# FCC_MCU.net
KiCad netlist of a schematic drawn in Altium Designer
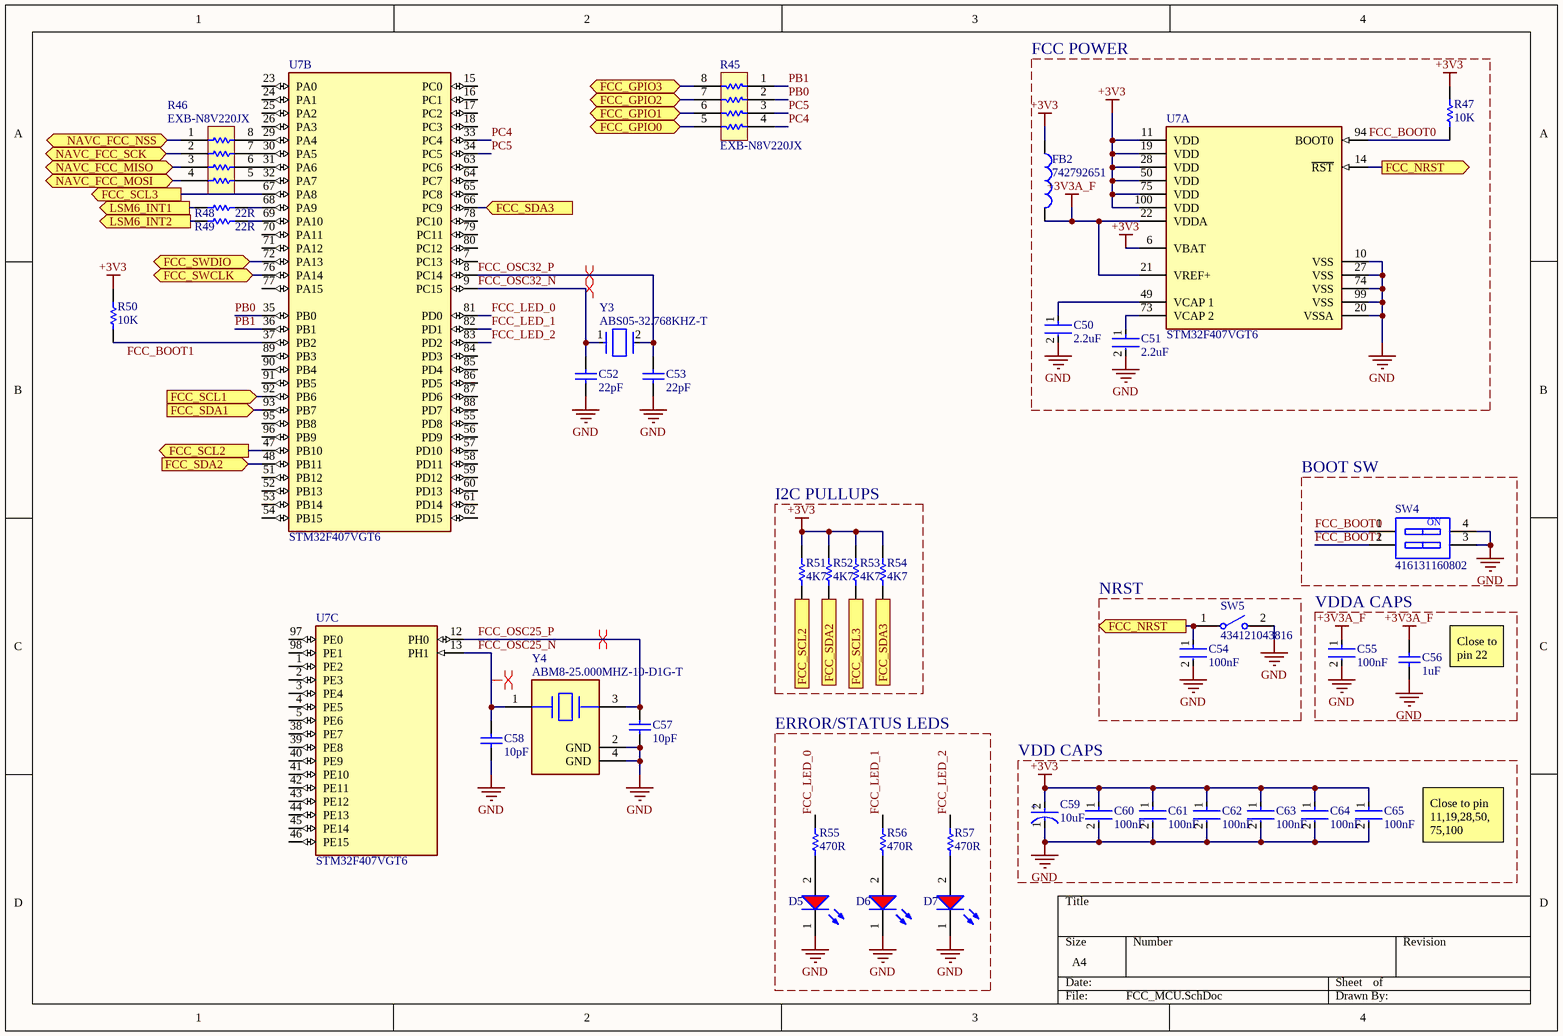
[diagram p0: FCC_MCU.SchDoc]

(export (version "E")
  (design (tool "Eeschema 10.0.6"))
  (components
    (comp (ref "C50")
      (value "2.2uF")
      (footprint "FP-CGA3E-0_3-0_1-IPC_A")
      (description "Cap Ceramic 100nF 50V X7R 10% Pad SMD 0603 +125°C Automotive T/R")
      (fields (field (name "TOLERANCE") "10%") (field (name "VOLTAGE") "50V"))
      (libsource (lib "Altium Content Vault") (part "b4654b650e69147ec39a6b967a45e02"))
    )
    (comp (ref "C51")
      (value "2.2uF")
      (footprint "FP-CGA3E-0_3-0_1-IPC_A")
      (description "Cap Ceramic 100nF 50V X7R 10% Pad SMD 0603 +125°C Automotive T/R")
      (fields (field (name "TOLERANCE") "10%") (field (name "VOLTAGE") "50V"))
      (libsource (lib "Altium Content Vault") (part "b4654b650e69147ec39a6b967a45e02"))
    )
    (comp (ref "C52")
      (value "22pF")
      (footprint "CAPC1608X90X35ML10T15")
      (description "Chip Capacitor, 22 pF, +/- 5%, 50 V, -55 to 125 degC, 0603 (1608 Metric), RoHS, Tape and Reel")
      (fields (field (name "MANUFACTURER") "Murata"))
      (libsource (lib "Altium Content Vault") (part "CAP-NP-2"))
    )
    (comp (ref "C53")
      (value "22pF")
      (footprint "CAPC1608X90X35ML10T15")
      (description "Chip Capacitor, 22 pF, +/- 5%, 50 V, -55 to 125 degC, 0603 (1608 Metric), RoHS, Tape and Reel")
      (fields (field (name "MANUFACTURER") "Murata"))
      (libsource (lib "Altium Content Vault") (part "CAP-NP-2"))
    )
    (comp (ref "C54")
      (value "100nF")
      (footprint "FP-CGA3E-0_3-0_1-IPC_A")
      (description "Cap Ceramic 100nF 50V X7R 10% Pad SMD 0603 +125°C Automotive T/R")
      (fields (field (name "TOLERANCE") "10%") (field (name "VOLTAGE") "50V"))
      (libsource (lib "Altium Content Vault") (part "b4654b650e69147ec39a6b967a45e02"))
    )
    (comp (ref "C55")
      (value "100nF")
      (footprint "FP-CGA3E-0_3-0_1-IPC_A")
      (description "Cap Ceramic 100nF 50V X7R 10% Pad SMD 0603 +125°C Automotive T/R")
      (fields (field (name "TOLERANCE") "10%") (field (name "VOLTAGE") "50V"))
      (libsource (lib "Altium Content Vault") (part "b4654b650e69147ec39a6b967a45e02"))
    )
    (comp (ref "C56")
      (value "1uF")
      (footprint "CAPC1608X87X35LL15T15")
      (fields (field (name "PART NUMBER") "C0603C105K3RACTU") (field (name "MANUFACTURER") "Kemet"))
      (libsource (lib "Altium Content Vault") (part "CAP"))
    )
    (comp (ref "C57")
      (value "10pF")
      (footprint "CAPC1608X90X35LL10T15")
      (fields (field (name "PART NUMBER") "GRM1885C1H100JA01D") (field (name "MANUFACTURER") "Murata"))
      (libsource (lib "Altium Content Vault") (part "CAP"))
    )
    (comp (ref "C58")
      (value "10pF")
      (footprint "CAPC1608X90X35LL10T15")
      (fields (field (name "PART NUMBER") "GRM1885C1H100JA01D") (field (name "MANUFACTURER") "Murata"))
      (libsource (lib "Altium Content Vault") (part "CAP"))
    )
    (comp (ref "C59")
      (value "10uF")
      (footprint "FP-T491A106K006AT-MFG")
      (description "CAP TANT 10UF 10% 6.3V 1206")
      (fields (field (name "TOLERANCE") "10%") (field (name "VOLTAGE") "6.3V"))
      (libsource (lib "Altium Content Vault") (part "a00bbbee19879c290e62620ae7e47b1"))
    )
    (comp (ref "C60")
      (value "100nF")
      (footprint "FP-CGA3E-0_3-0_1-IPC_A")
      (description "Cap Ceramic 100nF 50V X7R 10% Pad SMD 0603 +125°C Automotive T/R")
      (fields (field (name "TOLERANCE") "10%") (field (name "VOLTAGE") "50V"))
      (libsource (lib "Altium Content Vault") (part "b4654b650e69147ec39a6b967a45e02"))
    )
    (comp (ref "C61")
      (value "100nF")
      (footprint "FP-CGA3E-0_3-0_1-IPC_A")
      (description "Cap Ceramic 100nF 50V X7R 10% Pad SMD 0603 +125°C Automotive T/R")
      (fields (field (name "TOLERANCE") "10%") (field (name "VOLTAGE") "50V"))
      (libsource (lib "Altium Content Vault") (part "b4654b650e69147ec39a6b967a45e02"))
    )
    (comp (ref "C62")
      (value "100nF")
      (footprint "FP-CGA3E-0_3-0_1-IPC_A")
      (description "Cap Ceramic 100nF 50V X7R 10% Pad SMD 0603 +125°C Automotive T/R")
      (fields (field (name "TOLERANCE") "10%") (field (name "VOLTAGE") "50V"))
      (libsource (lib "Altium Content Vault") (part "b4654b650e69147ec39a6b967a45e02"))
    )
    (comp (ref "C63")
      (value "100nF")
      (footprint "FP-CGA3E-0_3-0_1-IPC_A")
      (description "Cap Ceramic 100nF 50V X7R 10% Pad SMD 0603 +125°C Automotive T/R")
      (fields (field (name "TOLERANCE") "10%") (field (name "VOLTAGE") "50V"))
      (libsource (lib "Altium Content Vault") (part "b4654b650e69147ec39a6b967a45e02"))
    )
    (comp (ref "C64")
      (value "100nF")
      (footprint "FP-CGA3E-0_3-0_1-IPC_A")
      (description "Cap Ceramic 100nF 50V X7R 10% Pad SMD 0603 +125°C Automotive T/R")
      (fields (field (name "TOLERANCE") "10%") (field (name "VOLTAGE") "50V"))
      (libsource (lib "Altium Content Vault") (part "b4654b650e69147ec39a6b967a45e02"))
    )
    (comp (ref "C65")
      (value "100nF")
      (footprint "FP-CGA3E-0_3-0_1-IPC_A")
      (description "Cap Ceramic 100nF 50V X7R 10% Pad SMD 0603 +125°C Automotive T/R")
      (fields (field (name "TOLERANCE") "10%") (field (name "VOLTAGE") "50V"))
      (libsource (lib "Altium Content Vault") (part "b4654b650e69147ec39a6b967a45e02"))
    )
    (comp (ref "D5")
      (value "150120SS75000")
      (footprint "WL-SMCW_1206_150120xx75000")
      (description "Led, Red, 630 Nm, 1.9 V, 30 Ma, 60 Mcd Rohs Compliant: Yes")
      (libsource (lib "Altium Content Vault") (part "LED_Red_2A-1K"))
    )
    (comp (ref "D6")
      (value "150120SS75000")
      (footprint "WL-SMCW_1206_150120xx75000")
      (description "Led, Red, 630 Nm, 1.9 V, 30 Ma, 60 Mcd Rohs Compliant: Yes")
      (libsource (lib "Altium Content Vault") (part "LED_Red_2A-1K"))
    )
    (comp (ref "D7")
      (value "150120SS75000")
      (footprint "WL-SMCW_1206_150120xx75000")
      (description "Led, Red, 630 Nm, 1.9 V, 30 Ma, 60 Mcd Rohs Compliant: Yes")
      (libsource (lib "Altium Content Vault") (part "LED_Red_2A-1K"))
    )
    (comp (ref "FB2")
      (value "742792651")
      (footprint "WE-CBF_0603_L1.6W0.8H0.8_HC")
      (fields (field (name "TOLERANCE") "25%"))
      (libsource (lib "Altium Content Vault") (part "Ferrite"))
    )
    (comp (ref "R45")
      (value "EXB-N8V220JX")
      (footprint "BOUR-CAT10_V")
      (description "Chip Resistor Array, 22 Ohm, +/- 5%, -55 to 125 degC, 8-Pin SMD, RoHS, Tape and Reel")
      (fields (field (name "MANUFACTURER") "Bourns") (field (name "TOLERANCE") "±5%"))
      (libsource (lib "Altium Content Vault") (part "RES-P-8"))
    )
    (comp (ref "R46")
      (value "EXB-N8V220JX")
      (footprint "BOUR-CAT10_V")
      (description "Chip Resistor Array, 22 Ohm, +/- 5%, -55 to 125 degC, 8-Pin SMD, RoHS, Tape and Reel")
      (fields (field (name "MANUFACTURER") "Bourns") (field (name "TOLERANCE") "±5%"))
      (libsource (lib "") (part "RES-P-8_1"))
    )
    (comp (ref "R47")
      (value "10K")
      (footprint "RESC1608X55X25ML10T15")
      (description "Chip Resistor, 0 Ohm, +/- 5%, 0.1 W, -55 to 155 degC, 0603 (1608 Metric), RoHS, Tape and Reel")
      (fields (field (name "TOLERANCE") "5%") (field (name "MANUFACTURER") "Yageo"))
      (libsource (lib "Altium Content Vault") (part "RES-2"))
    )
    (comp (ref "R48")
      (value "22R")
      (footprint "RESC1608X55X25ML10T15")
      (description "Chip Resistor, 0 Ohm, +/- 5%, 0.1 W, -55 to 155 degC, 0603 (1608 Metric), RoHS, Tape and Reel")
      (fields (field (name "TOLERANCE") "5%") (field (name "MANUFACTURER") "Yageo"))
      (libsource (lib "Altium Content Vault") (part "RES-2"))
    )
    (comp (ref "R49")
      (value "22R")
      (footprint "RESC1608X55X25ML10T15")
      (description "Chip Resistor, 0 Ohm, +/- 5%, 0.1 W, -55 to 155 degC, 0603 (1608 Metric), RoHS, Tape and Reel")
      (fields (field (name "TOLERANCE") "5%") (field (name "MANUFACTURER") "Yageo"))
      (libsource (lib "Altium Content Vault") (part "RES-2"))
    )
    (comp (ref "R50")
      (value "10K")
      (footprint "RESC1608X55X25ML10T15")
      (description "Chip Resistor, 0 Ohm, +/- 5%, 0.1 W, -55 to 155 degC, 0603 (1608 Metric), RoHS, Tape and Reel")
      (fields (field (name "TOLERANCE") "5%") (field (name "MANUFACTURER") "Yageo"))
      (libsource (lib "Altium Content Vault") (part "RES-2"))
    )
    (comp (ref "R51")
      (value "4K7")
      (footprint "RESC1608X55X25ML10T15")
      (description "Chip Resistor, 0 Ohm, +/- 5%, 0.1 W, -55 to 155 degC, 0603 (1608 Metric), RoHS, Tape and Reel")
      (fields (field (name "TOLERANCE") "5%") (field (name "MANUFACTURER") "Yageo"))
      (libsource (lib "Altium Content Vault") (part "RES-2"))
    )
    (comp (ref "R52")
      (value "4K7")
      (footprint "RESC1608X55X25ML10T15")
      (description "Chip Resistor, 0 Ohm, +/- 5%, 0.1 W, -55 to 155 degC, 0603 (1608 Metric), RoHS, Tape and Reel")
      (fields (field (name "TOLERANCE") "5%") (field (name "MANUFACTURER") "Yageo"))
      (libsource (lib "Altium Content Vault") (part "RES-2"))
    )
    (comp (ref "R53")
      (value "4K7")
      (footprint "RESC1608X55X25ML10T15")
      (description "Chip Resistor, 0 Ohm, +/- 5%, 0.1 W, -55 to 155 degC, 0603 (1608 Metric), RoHS, Tape and Reel")
      (fields (field (name "TOLERANCE") "5%") (field (name "MANUFACTURER") "Yageo"))
      (libsource (lib "Altium Content Vault") (part "RES-2"))
    )
    (comp (ref "R54")
      (value "4K7")
      (footprint "RESC1608X55X25ML10T15")
      (description "Chip Resistor, 0 Ohm, +/- 5%, 0.1 W, -55 to 155 degC, 0603 (1608 Metric), RoHS, Tape and Reel")
      (fields (field (name "TOLERANCE") "5%") (field (name "MANUFACTURER") "Yageo"))
      (libsource (lib "Altium Content Vault") (part "RES-2"))
    )
    (comp (ref "R55")
      (value "470R")
      (footprint "RESC1609X50X30NL8T20")
      (description "Chip Resistor, 0 Ohm, Jumper, 100 mW, -55 to 155 degC, 0603 (1608 Metric), RoHS, Tape and Reel")
      (fields (field (name "MANUFACTURER") "Vishay Semiconductor"))
      (libsource (lib "Altium Content Vault") (part "RES-2"))
    )
    (comp (ref "R56")
      (value "470R")
      (footprint "RESC1609X50X30NL8T20")
      (description "Chip Resistor, 0 Ohm, Jumper, 100 mW, -55 to 155 degC, 0603 (1608 Metric), RoHS, Tape and Reel")
      (fields (field (name "MANUFACTURER") "Vishay Semiconductor"))
      (libsource (lib "Altium Content Vault") (part "RES-2"))
    )
    (comp (ref "R57")
      (value "470R")
      (footprint "RESC1609X50X30NL8T20")
      (description "Chip Resistor, 0 Ohm, Jumper, 100 mW, -55 to 155 degC, 0603 (1608 Metric), RoHS, Tape and Reel")
      (fields (field (name "MANUFACTURER") "Vishay Semiconductor"))
      (libsource (lib "Altium Content Vault") (part "RES-2"))
    )
    (comp (ref "SW4")
      (value "416131160802")
      (footprint "416131160802")
      (libsource (lib "Altium Content Vault") (part "DIP-2"))
    )
    (comp (ref "SW5")
      (value "434121043816")
      (footprint "434121043816")
      (description "Switch Tactile Spst-no 0.05A 12V")
      (libsource (lib "Altium Content Vault") (part "SPST-NO_2P"))
    )
    (comp (ref "U7")
      (value "STM32F407VGT6")
      (footprint "FP-LQFP100-1L-MFG")
      (libsource (lib "Altium Content Vault") (part "a7eb53df74ca670d391abe4a9ac8be5"))
    )
    (comp (ref "Y3")
      (value "ABS05-32.768KHZ-T")
      (footprint "FP-ABS05-MFG")
      (description "Crystal 32.768kHz ±20ppm (Tol) 12.5pF FUND 90kΩ 2-Pin SMD T/R")
      (fields (field (name "TOLERANCE") "20ppm"))
      (libsource (lib "Altium Content Vault") (part "c23a69dc6c9e2f18f2079038eb95dd1"))
    )
    (comp (ref "Y4")
      (value "ABM8-25.000MHZ-10-D1G-T")
      (footprint "FP-ABM8-MFG")
      (description "Crystal 25MHz ±10ppm 10pF SMD-4 3.2mm x 2.5mm")
      (libsource (lib "Altium Content Vault") (part "dfdb7f9a12507849fb681da9a70121c"))
    )
  )
  (nets
    (net (code "1") (name "+3V3") (class "Default")
      (node (ref "C59") (pin "2") (pinfunction "A_2") (pintype "passive"))
      (node (ref "C60") (pin "1") (pinfunction "1_1") (pintype "passive"))
      (node (ref "C61") (pin "1") (pinfunction "1_1") (pintype "passive"))
      (node (ref "C62") (pin "1") (pinfunction "1_1") (pintype "passive"))
      (node (ref "C63") (pin "1") (pinfunction "1_1") (pintype "passive"))
      (node (ref "C64") (pin "1") (pinfunction "1_1") (pintype "passive"))
      (node (ref "C65") (pin "1") (pinfunction "1_1") (pintype "passive"))
      (node (ref "FB2") (pin "1") (pinfunction "1_1") (pintype "passive"))
      (node (ref "R47") (pin "1") (pinfunction "1_1") (pintype "passive"))
      (node (ref "R50") (pin "1") (pinfunction "1_1") (pintype "passive"))
      (node (ref "R51") (pin "2") (pinfunction "2_2") (pintype "passive"))
      (node (ref "R52") (pin "2") (pinfunction "2_2") (pintype "passive"))
      (node (ref "R53") (pin "2") (pinfunction "2_2") (pintype "passive"))
      (node (ref "R54") (pin "2") (pinfunction "2_2") (pintype "passive"))
      (node (ref "U7") (pin "100") (pinfunction "VDD_100") (pintype "power_in"))
      (node (ref "U7") (pin "11") (pinfunction "VDD_11") (pintype "power_in"))
      (node (ref "U7") (pin "19") (pinfunction "VDD_19") (pintype "power_in"))
      (node (ref "U7") (pin "28") (pinfunction "VDD_28") (pintype "power_in"))
      (node (ref "U7") (pin "50") (pinfunction "VDD_50") (pintype "power_in"))
      (node (ref "U7") (pin "6") (pinfunction "VBAT_6") (pintype "power_in"))
      (node (ref "U7") (pin "75") (pinfunction "VDD_75") (pintype "power_in"))
    )
    (net (code "2") (name "+3V3A_F") (class "Default")
      (node (ref "C55") (pin "1") (pinfunction "1_1") (pintype "passive"))
      (node (ref "C56") (pin "2") (pinfunction "2_2") (pintype "passive"))
      (node (ref "FB2") (pin "2") (pinfunction "2_2") (pintype "passive"))
      (node (ref "U7") (pin "21") (pinfunction "VREF+_21") (pintype "power_in"))
      (node (ref "U7") (pin "22") (pinfunction "VDDA_22") (pintype "power_in"))
    )
    (net (code "3") (name "/FCC_BOOT0") (class "Default")
      (node (ref "R47") (pin "2") (pinfunction "2_2") (pintype "passive"))
      (node (ref "SW4") (pin "1") (pinfunction "1_1") (pintype "passive"))
      (node (ref "U7") (pin "94") (pinfunction "BOOT0_94") (pintype "input"))
    )
    (net (code "4") (name "/FCC_BOOT1") (class "Default")
      (node (ref "R50") (pin "2") (pinfunction "2_2") (pintype "passive"))
      (node (ref "SW4") (pin "2") (pinfunction "2_2") (pintype "passive"))
      (node (ref "U7") (pin "37") (pinfunction "PB2_37") (pintype "bidirectional"))
    )
    (net (code "5") (name "/FCC_GPIO0") (class "Default")
      (node (ref "R45") (pin "5") (pinfunction "5_5") (pintype "passive"))
    )
    (net (code "6") (name "/FCC_GPIO1") (class "Default")
      (node (ref "R45") (pin "6") (pinfunction "6_6") (pintype "passive"))
    )
    (net (code "7") (name "/FCC_GPIO2") (class "Default")
      (node (ref "R45") (pin "7") (pinfunction "7_7") (pintype "passive"))
    )
    (net (code "8") (name "/FCC_GPIO3") (class "Default")
      (node (ref "R45") (pin "8") (pinfunction "8_8") (pintype "passive"))
    )
    (net (code "9") (name "/FCC_LED_0") (class "Default")
      (node (ref "R55") (pin "1") (pinfunction "1_1") (pintype "passive"))
      (node (ref "U7") (pin "81") (pinfunction "PD0_81") (pintype "bidirectional"))
    )
    (net (code "10") (name "/FCC_LED_1") (class "Default")
      (node (ref "R56") (pin "1") (pinfunction "1_1") (pintype "passive"))
      (node (ref "U7") (pin "82") (pinfunction "PD1_82") (pintype "bidirectional"))
    )
    (net (code "11") (name "/FCC_LED_2") (class "Default")
      (node (ref "R57") (pin "1") (pinfunction "1_1") (pintype "passive"))
      (node (ref "U7") (pin "83") (pinfunction "PD2_83") (pintype "bidirectional"))
    )
    (net (code "12") (name "/FCC_NRST") (class "Default")
      (node (ref "C54") (pin "1") (pinfunction "1_1") (pintype "passive"))
      (node (ref "SW5") (pin "1") (pinfunction "1_1") (pintype "passive"))
      (node (ref "U7") (pin "14") (pinfunction "~{RST}_14") (pintype "input"))
    )
    (net (code "13") (name "/FCC_OSC25_N") (class "Default")
      (node (ref "C58") (pin "2") (pinfunction "2_2") (pintype "passive"))
      (node (ref "U7") (pin "13") (pinfunction "PH1_13") (pintype "input"))
      (node (ref "Y4") (pin "1") (pinfunction "1_1") (pintype "passive"))
    )
    (net (code "14") (name "/FCC_OSC25_P") (class "Default")
      (node (ref "C57") (pin "2") (pinfunction "2_2") (pintype "passive"))
      (node (ref "U7") (pin "12") (pinfunction "PH0_12") (pintype "bidirectional"))
      (node (ref "Y4") (pin "3") (pinfunction "3_3") (pintype "passive"))
    )
    (net (code "15") (name "/FCC_OSC32_N") (class "Default")
      (node (ref "C52") (pin "2") (pinfunction "2_2") (pintype "passive"))
      (node (ref "U7") (pin "9") (pinfunction "PC15_9") (pintype "bidirectional"))
      (node (ref "Y3") (pin "1") (pinfunction "1_1") (pintype "passive"))
    )
    (net (code "16") (name "/FCC_OSC32_P") (class "Default")
      (node (ref "C53") (pin "2") (pinfunction "2_2") (pintype "passive"))
      (node (ref "U7") (pin "8") (pinfunction "PC14_8") (pintype "bidirectional"))
      (node (ref "Y3") (pin "2") (pinfunction "2_2") (pintype "passive"))
    )
    (net (code "17") (name "/FCC_SCL1") (class "Default")
      (node (ref "U7") (pin "92") (pinfunction "PB6_92") (pintype "bidirectional"))
    )
    (net (code "18") (name "/FCC_SCL2") (class "Default")
      (node (ref "R51") (pin "1") (pinfunction "1_1") (pintype "passive"))
      (node (ref "U7") (pin "47") (pinfunction "PB10_47") (pintype "bidirectional"))
    )
    (net (code "19") (name "/FCC_SCL3") (class "Default")
      (node (ref "R53") (pin "1") (pinfunction "1_1") (pintype "passive"))
      (node (ref "U7") (pin "67") (pinfunction "PA8_67") (pintype "bidirectional"))
    )
    (net (code "20") (name "/FCC_SDA1") (class "Default")
      (node (ref "U7") (pin "93") (pinfunction "PB7_93") (pintype "bidirectional"))
    )
    (net (code "21") (name "/FCC_SDA2") (class "Default")
      (node (ref "R52") (pin "1") (pinfunction "1_1") (pintype "passive"))
      (node (ref "U7") (pin "48") (pinfunction "PB11_48") (pintype "bidirectional"))
    )
    (net (code "22") (name "/FCC_SDA3") (class "Default")
      (node (ref "R54") (pin "1") (pinfunction "1_1") (pintype "passive"))
      (node (ref "U7") (pin "66") (pinfunction "PC9_66") (pintype "bidirectional"))
    )
    (net (code "23") (name "/FCC_SWCLK") (class "Default")
      (node (ref "U7") (pin "76") (pinfunction "PA14_76") (pintype "bidirectional"))
    )
    (net (code "24") (name "/FCC_SWDIO") (class "Default")
      (node (ref "U7") (pin "72") (pinfunction "PA13_72") (pintype "bidirectional"))
    )
    (net (code "25") (name "/LSM6_INT1") (class "Default")
      (node (ref "R48") (pin "1") (pinfunction "1_1") (pintype "passive"))
    )
    (net (code "26") (name "/LSM6_INT2") (class "Default")
      (node (ref "R49") (pin "1") (pinfunction "1_1") (pintype "passive"))
    )
    (net (code "27") (name "/NAVC_FCC_MISO") (class "Default")
      (node (ref "R46") (pin "3") (pinfunction "3_3") (pintype "passive"))
    )
    (net (code "28") (name "/NAVC_FCC_MOSI") (class "Default")
      (node (ref "R46") (pin "4") (pinfunction "4_4") (pintype "passive"))
    )
    (net (code "29") (name "/NAVC_FCC_NSS") (class "Default")
      (node (ref "R46") (pin "1") (pinfunction "1_1") (pintype "passive"))
    )
    (net (code "30") (name "/NAVC_FCC_SCK") (class "Default")
      (node (ref "R46") (pin "2") (pinfunction "2_2") (pintype "passive"))
    )
    (net (code "31") (name "/PB0") (class "Default")
      (node (ref "R45") (pin "2") (pinfunction "2_2") (pintype "passive"))
      (node (ref "U7") (pin "35") (pinfunction "PB0_35") (pintype "bidirectional"))
    )
    (net (code "32") (name "/PB1") (class "Default")
      (node (ref "R45") (pin "1") (pinfunction "1_1") (pintype "passive"))
      (node (ref "U7") (pin "36") (pinfunction "PB1_36") (pintype "bidirectional"))
    )
    (net (code "33") (name "/PC4") (class "Default")
      (node (ref "R45") (pin "4") (pinfunction "4_4") (pintype "passive"))
      (node (ref "U7") (pin "33") (pinfunction "PC4_33") (pintype "bidirectional"))
    )
    (net (code "34") (name "/PC5") (class "Default")
      (node (ref "R45") (pin "3") (pinfunction "3_3") (pintype "passive"))
      (node (ref "U7") (pin "34") (pinfunction "PC5_34") (pintype "bidirectional"))
    )
    (net (code "35") (name "GND") (class "Default")
      (node (ref "C50") (pin "2") (pinfunction "2_2") (pintype "passive"))
      (node (ref "C51") (pin "2") (pinfunction "2_2") (pintype "passive"))
      (node (ref "C52") (pin "1") (pinfunction "1_1") (pintype "passive"))
      (node (ref "C53") (pin "1") (pinfunction "1_1") (pintype "passive"))
      (node (ref "C54") (pin "2") (pinfunction "2_2") (pintype "passive"))
      (node (ref "C55") (pin "2") (pinfunction "2_2") (pintype "passive"))
      (node (ref "C56") (pin "1") (pinfunction "1_1") (pintype "passive"))
      (node (ref "C57") (pin "1") (pinfunction "1_1") (pintype "passive"))
      (node (ref "C58") (pin "1") (pinfunction "1_1") (pintype "passive"))
      (node (ref "C59") (pin "1") (pinfunction "C_1") (pintype "passive"))
      (node (ref "C60") (pin "2") (pinfunction "2_2") (pintype "passive"))
      (node (ref "C61") (pin "2") (pinfunction "2_2") (pintype "passive"))
      (node (ref "C62") (pin "2") (pinfunction "2_2") (pintype "passive"))
      (node (ref "C63") (pin "2") (pinfunction "2_2") (pintype "passive"))
      (node (ref "C64") (pin "2") (pinfunction "2_2") (pintype "passive"))
      (node (ref "C65") (pin "2") (pinfunction "2_2") (pintype "passive"))
      (node (ref "D5") (pin "1") (pinfunction "K_1") (pintype "passive"))
      (node (ref "D6") (pin "1") (pinfunction "K_1") (pintype "passive"))
      (node (ref "D7") (pin "1") (pinfunction "K_1") (pintype "passive"))
      (node (ref "SW4") (pin "3") (pinfunction "3_3") (pintype "passive"))
      (node (ref "SW4") (pin "4") (pinfunction "4_4") (pintype "passive"))
      (node (ref "SW5") (pin "2") (pinfunction "2_2") (pintype "passive"))
      (node (ref "U7") (pin "10") (pinfunction "VSS_10") (pintype "power_in"))
      (node (ref "U7") (pin "20") (pinfunction "VSSA_20") (pintype "power_in"))
      (node (ref "U7") (pin "27") (pinfunction "VSS_27") (pintype "power_in"))
      (node (ref "U7") (pin "74") (pinfunction "VSS_74") (pintype "power_in"))
      (node (ref "U7") (pin "99") (pinfunction "VSS_99") (pintype "power_in"))
      (node (ref "Y4") (pin "2") (pinfunction "GND_2") (pintype "power_in"))
      (node (ref "Y4") (pin "4") (pinfunction "GND_4") (pintype "power_in"))
    )
    (net (code "36") (name "Net-(D5-A)") (class "Default")
      (node (ref "D5") (pin "2") (pinfunction "A_2") (pintype "passive"))
      (node (ref "R55") (pin "2") (pinfunction "2_2") (pintype "passive"))
    )
    (net (code "37") (name "Net-(D6-A)") (class "Default")
      (node (ref "D6") (pin "2") (pinfunction "A_2") (pintype "passive"))
      (node (ref "R56") (pin "2") (pinfunction "2_2") (pintype "passive"))
    )
    (net (code "38") (name "Net-(D7-A)") (class "Default")
      (node (ref "D7") (pin "2") (pinfunction "A_2") (pintype "passive"))
      (node (ref "R57") (pin "2") (pinfunction "2_2") (pintype "passive"))
    )
    (net (code "39") (name "Net-(U7A-VCAP_1)") (class "Default")
      (node (ref "C50") (pin "1") (pinfunction "1_1") (pintype "passive"))
      (node (ref "U7") (pin "49") (pinfunction "VCAP_1_49") (pintype "power_in"))
    )
    (net (code "40") (name "Net-(U7A-VCAP_2)") (class "Default")
      (node (ref "C51") (pin "1") (pinfunction "1_1") (pintype "passive"))
      (node (ref "U7") (pin "73") (pinfunction "VCAP_2_73") (pintype "power_in"))
    )
    (net (code "41") (name "Net-(U7B-PA4)") (class "Default")
      (node (ref "R46") (pin "8") (pinfunction "8_8") (pintype "passive"))
      (node (ref "U7") (pin "29") (pinfunction "PA4_29") (pintype "bidirectional"))
    )
    (net (code "42") (name "Net-(U7B-PA5)") (class "Default")
      (node (ref "R46") (pin "7") (pinfunction "7_7") (pintype "passive"))
      (node (ref "U7") (pin "30") (pinfunction "PA5_30") (pintype "bidirectional"))
    )
    (net (code "43") (name "Net-(U7B-PA6)") (class "Default")
      (node (ref "R46") (pin "6") (pinfunction "6_6") (pintype "passive"))
      (node (ref "U7") (pin "31") (pinfunction "PA6_31") (pintype "bidirectional"))
    )
    (net (code "44") (name "Net-(U7B-PA7)") (class "Default")
      (node (ref "R46") (pin "5") (pinfunction "5_5") (pintype "passive"))
      (node (ref "U7") (pin "32") (pinfunction "PA7_32") (pintype "bidirectional"))
    )
    (net (code "45") (name "Net-(U7B-PA9)") (class "Default")
      (node (ref "R48") (pin "2") (pinfunction "2_2") (pintype "passive"))
      (node (ref "U7") (pin "68") (pinfunction "PA9_68") (pintype "bidirectional"))
    )
    (net (code "46") (name "Net-(U7B-PA10)") (class "Default")
      (node (ref "R49") (pin "2") (pinfunction "2_2") (pintype "passive"))
      (node (ref "U7") (pin "69") (pinfunction "PA10_69") (pintype "bidirectional"))
    )
    (net (code "47") (name "unconnected-(U7B-PA0-Pad23)") (class "Default")
      (node (ref "U7") (pin "23") (pinfunction "PA0_23") (pintype "bidirectional"))
    )
    (net (code "48") (name "unconnected-(U7B-PA1-Pad24)") (class "Default")
      (node (ref "U7") (pin "24") (pinfunction "PA1_24") (pintype "bidirectional"))
    )
    (net (code "49") (name "unconnected-(U7B-PA2-Pad25)") (class "Default")
      (node (ref "U7") (pin "25") (pinfunction "PA2_25") (pintype "bidirectional"))
    )
    (net (code "50") (name "unconnected-(U7B-PA3-Pad26)") (class "Default")
      (node (ref "U7") (pin "26") (pinfunction "PA3_26") (pintype "bidirectional"))
    )
    (net (code "51") (name "unconnected-(U7B-PA11-Pad70)") (class "Default")
      (node (ref "U7") (pin "70") (pinfunction "PA11_70") (pintype "bidirectional"))
    )
    (net (code "52") (name "unconnected-(U7B-PA12-Pad71)") (class "Default")
      (node (ref "U7") (pin "71") (pinfunction "PA12_71") (pintype "bidirectional"))
    )
    (net (code "53") (name "unconnected-(U7B-PA15-Pad77)") (class "Default")
      (node (ref "U7") (pin "77") (pinfunction "PA15_77") (pintype "bidirectional"))
    )
    (net (code "54") (name "unconnected-(U7B-PB3-Pad89)") (class "Default")
      (node (ref "U7") (pin "89") (pinfunction "PB3_89") (pintype "bidirectional"))
    )
    (net (code "55") (name "unconnected-(U7B-PB4-Pad90)") (class "Default")
      (node (ref "U7") (pin "90") (pinfunction "PB4_90") (pintype "bidirectional"))
    )
    (net (code "56") (name "unconnected-(U7B-PB5-Pad91)") (class "Default")
      (node (ref "U7") (pin "91") (pinfunction "PB5_91") (pintype "bidirectional"))
    )
    (net (code "57") (name "unconnected-(U7B-PB8-Pad95)") (class "Default")
      (node (ref "U7") (pin "95") (pinfunction "PB8_95") (pintype "bidirectional"))
    )
    (net (code "58") (name "unconnected-(U7B-PB9-Pad96)") (class "Default")
      (node (ref "U7") (pin "96") (pinfunction "PB9_96") (pintype "bidirectional"))
    )
    (net (code "59") (name "unconnected-(U7B-PB12-Pad51)") (class "Default")
      (node (ref "U7") (pin "51") (pinfunction "PB12_51") (pintype "bidirectional"))
    )
    (net (code "60") (name "unconnected-(U7B-PB13-Pad52)") (class "Default")
      (node (ref "U7") (pin "52") (pinfunction "PB13_52") (pintype "bidirectional"))
    )
    (net (code "61") (name "unconnected-(U7B-PB14-Pad53)") (class "Default")
      (node (ref "U7") (pin "53") (pinfunction "PB14_53") (pintype "bidirectional"))
    )
    (net (code "62") (name "unconnected-(U7B-PB15-Pad54)") (class "Default")
      (node (ref "U7") (pin "54") (pinfunction "PB15_54") (pintype "bidirectional"))
    )
    (net (code "63") (name "unconnected-(U7B-PC0-Pad15)") (class "Default")
      (node (ref "U7") (pin "15") (pinfunction "PC0_15") (pintype "bidirectional"))
    )
    (net (code "64") (name "unconnected-(U7B-PC1-Pad16)") (class "Default")
      (node (ref "U7") (pin "16") (pinfunction "PC1_16") (pintype "bidirectional"))
    )
    (net (code "65") (name "unconnected-(U7B-PC2-Pad17)") (class "Default")
      (node (ref "U7") (pin "17") (pinfunction "PC2_17") (pintype "bidirectional"))
    )
    (net (code "66") (name "unconnected-(U7B-PC3-Pad18)") (class "Default")
      (node (ref "U7") (pin "18") (pinfunction "PC3_18") (pintype "bidirectional"))
    )
    (net (code "67") (name "unconnected-(U7B-PC6-Pad63)") (class "Default")
      (node (ref "U7") (pin "63") (pinfunction "PC6_63") (pintype "bidirectional"))
    )
    (net (code "68") (name "unconnected-(U7B-PC7-Pad64)") (class "Default")
      (node (ref "U7") (pin "64") (pinfunction "PC7_64") (pintype "bidirectional"))
    )
    (net (code "69") (name "unconnected-(U7B-PC8-Pad65)") (class "Default")
      (node (ref "U7") (pin "65") (pinfunction "PC8_65") (pintype "bidirectional"))
    )
    (net (code "70") (name "unconnected-(U7B-PC10-Pad78)") (class "Default")
      (node (ref "U7") (pin "78") (pinfunction "PC10_78") (pintype "bidirectional"))
    )
    (net (code "71") (name "unconnected-(U7B-PC11-Pad79)") (class "Default")
      (node (ref "U7") (pin "79") (pinfunction "PC11_79") (pintype "bidirectional"))
    )
    (net (code "72") (name "unconnected-(U7B-PC12-Pad80)") (class "Default")
      (node (ref "U7") (pin "80") (pinfunction "PC12_80") (pintype "bidirectional"))
    )
    (net (code "73") (name "unconnected-(U7B-PC13-Pad7)") (class "Default")
      (node (ref "U7") (pin "7") (pinfunction "PC13_7") (pintype "bidirectional"))
    )
    (net (code "74") (name "unconnected-(U7B-PD3-Pad84)") (class "Default")
      (node (ref "U7") (pin "84") (pinfunction "PD3_84") (pintype "bidirectional"))
    )
    (net (code "75") (name "unconnected-(U7B-PD4-Pad85)") (class "Default")
      (node (ref "U7") (pin "85") (pinfunction "PD4_85") (pintype "bidirectional"))
    )
    (net (code "76") (name "unconnected-(U7B-PD5-Pad86)") (class "Default")
      (node (ref "U7") (pin "86") (pinfunction "PD5_86") (pintype "bidirectional"))
    )
    (net (code "77") (name "unconnected-(U7B-PD6-Pad87)") (class "Default")
      (node (ref "U7") (pin "87") (pinfunction "PD6_87") (pintype "bidirectional"))
    )
    (net (code "78") (name "unconnected-(U7B-PD7-Pad88)") (class "Default")
      (node (ref "U7") (pin "88") (pinfunction "PD7_88") (pintype "bidirectional"))
    )
    (net (code "79") (name "unconnected-(U7B-PD8-Pad55)") (class "Default")
      (node (ref "U7") (pin "55") (pinfunction "PD8_55") (pintype "bidirectional"))
    )
    (net (code "80") (name "unconnected-(U7B-PD9-Pad56)") (class "Default")
      (node (ref "U7") (pin "56") (pinfunction "PD9_56") (pintype "bidirectional"))
    )
    (net (code "81") (name "unconnected-(U7B-PD10-Pad57)") (class "Default")
      (node (ref "U7") (pin "57") (pinfunction "PD10_57") (pintype "bidirectional"))
    )
    (net (code "82") (name "unconnected-(U7B-PD11-Pad58)") (class "Default")
      (node (ref "U7") (pin "58") (pinfunction "PD11_58") (pintype "bidirectional"))
    )
    (net (code "83") (name "unconnected-(U7B-PD12-Pad59)") (class "Default")
      (node (ref "U7") (pin "59") (pinfunction "PD12_59") (pintype "bidirectional"))
    )
    (net (code "84") (name "unconnected-(U7B-PD13-Pad60)") (class "Default")
      (node (ref "U7") (pin "60") (pinfunction "PD13_60") (pintype "bidirectional"))
    )
    (net (code "85") (name "unconnected-(U7B-PD14-Pad61)") (class "Default")
      (node (ref "U7") (pin "61") (pinfunction "PD14_61") (pintype "bidirectional"))
    )
    (net (code "86") (name "unconnected-(U7B-PD15-Pad62)") (class "Default")
      (node (ref "U7") (pin "62") (pinfunction "PD15_62") (pintype "bidirectional"))
    )
    (net (code "87") (name "unconnected-(U7C-PE0-Pad97)") (class "Default")
      (node (ref "U7") (pin "97") (pinfunction "PE0_97") (pintype "bidirectional"))
    )
    (net (code "88") (name "unconnected-(U7C-PE1-Pad98)") (class "Default")
      (node (ref "U7") (pin "98") (pinfunction "PE1_98") (pintype "bidirectional"))
    )
    (net (code "89") (name "unconnected-(U7C-PE2-Pad1)") (class "Default")
      (node (ref "U7") (pin "1") (pinfunction "PE2_1") (pintype "bidirectional"))
    )
    (net (code "90") (name "unconnected-(U7C-PE3-Pad2)") (class "Default")
      (node (ref "U7") (pin "2") (pinfunction "PE3_2") (pintype "bidirectional"))
    )
    (net (code "91") (name "unconnected-(U7C-PE4-Pad3)") (class "Default")
      (node (ref "U7") (pin "3") (pinfunction "PE4_3") (pintype "bidirectional"))
    )
    (net (code "92") (name "unconnected-(U7C-PE5-Pad4)") (class "Default")
      (node (ref "U7") (pin "4") (pinfunction "PE5_4") (pintype "bidirectional"))
    )
    (net (code "93") (name "unconnected-(U7C-PE6-Pad5)") (class "Default")
      (node (ref "U7") (pin "5") (pinfunction "PE6_5") (pintype "bidirectional"))
    )
    (net (code "94") (name "unconnected-(U7C-PE7-Pad38)") (class "Default")
      (node (ref "U7") (pin "38") (pinfunction "PE7_38") (pintype "bidirectional"))
    )
    (net (code "95") (name "unconnected-(U7C-PE8-Pad39)") (class "Default")
      (node (ref "U7") (pin "39") (pinfunction "PE8_39") (pintype "bidirectional"))
    )
    (net (code "96") (name "unconnected-(U7C-PE9-Pad40)") (class "Default")
      (node (ref "U7") (pin "40") (pinfunction "PE9_40") (pintype "bidirectional"))
    )
    (net (code "97") (name "unconnected-(U7C-PE10-Pad41)") (class "Default")
      (node (ref "U7") (pin "41") (pinfunction "PE10_41") (pintype "bidirectional"))
    )
    (net (code "98") (name "unconnected-(U7C-PE11-Pad42)") (class "Default")
      (node (ref "U7") (pin "42") (pinfunction "PE11_42") (pintype "bidirectional"))
    )
    (net (code "99") (name "unconnected-(U7C-PE12-Pad43)") (class "Default")
      (node (ref "U7") (pin "43") (pinfunction "PE12_43") (pintype "bidirectional"))
    )
    (net (code "100") (name "unconnected-(U7C-PE13-Pad44)") (class "Default")
      (node (ref "U7") (pin "44") (pinfunction "PE13_44") (pintype "bidirectional"))
    )
    (net (code "101") (name "unconnected-(U7C-PE14-Pad45)") (class "Default")
      (node (ref "U7") (pin "45") (pinfunction "PE14_45") (pintype "bidirectional"))
    )
    (net (code "102") (name "unconnected-(U7C-PE15-Pad46)") (class "Default")
      (node (ref "U7") (pin "46") (pinfunction "PE15_46") (pintype "bidirectional"))
    )
  )
)
